# Peripherals.net
KiCad netlist of a schematic drawn in Altium Designer
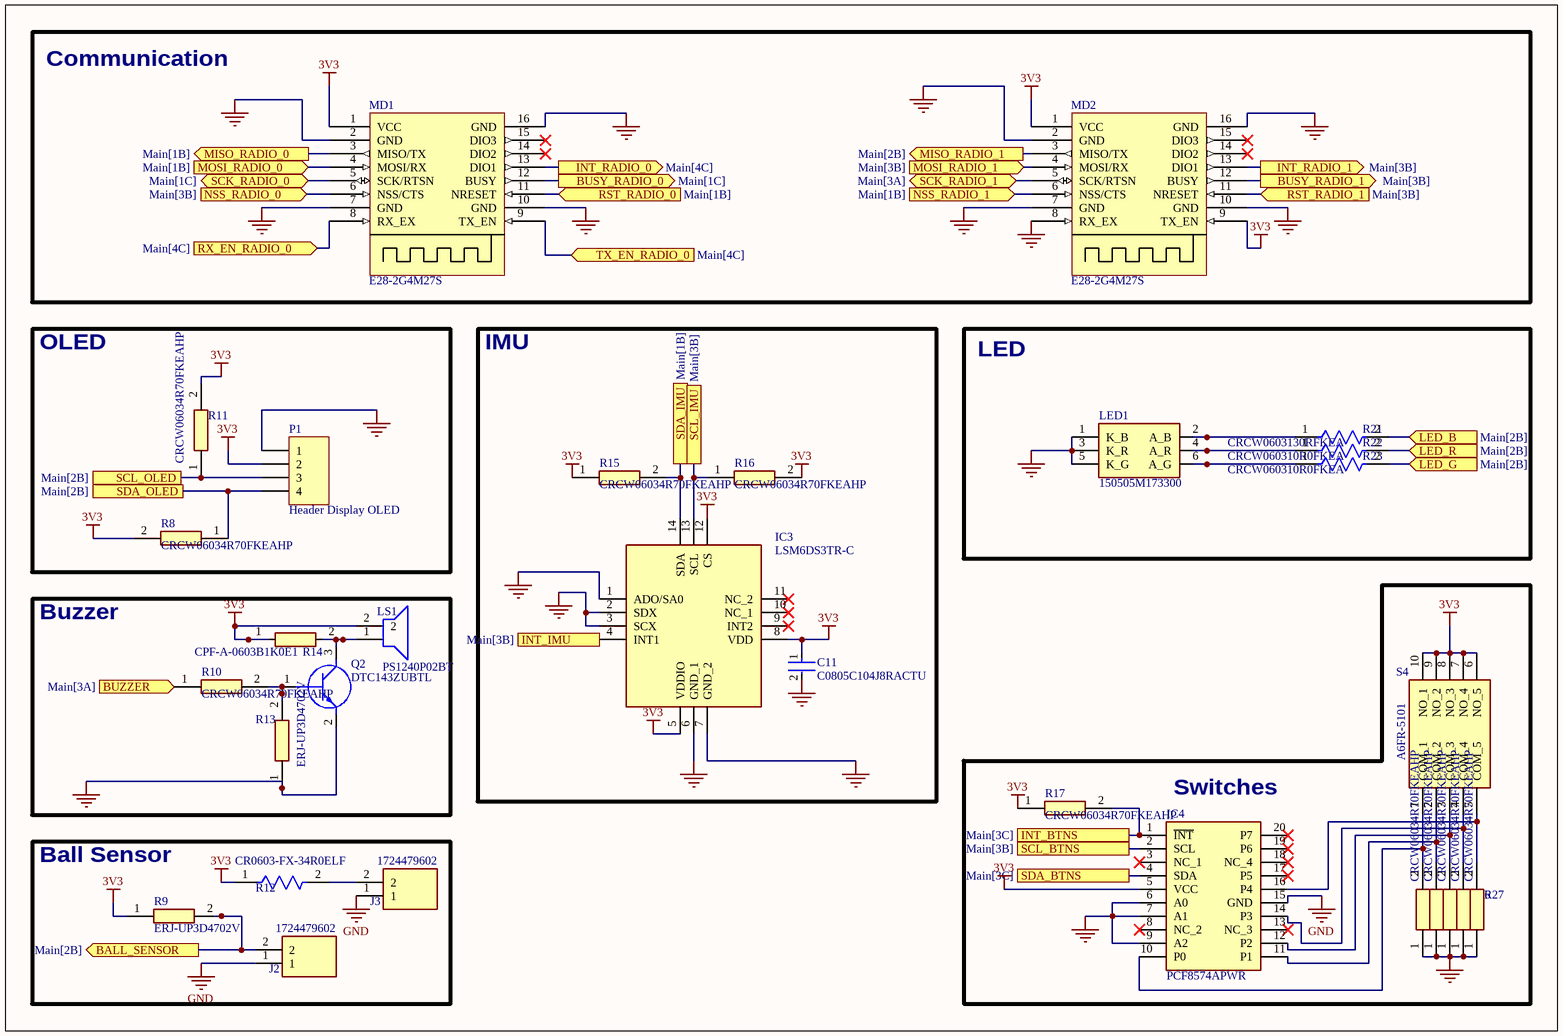
[diagram p0: Peripherals.SchDoc]

(export (version "E")
  (design (tool "Eeschema 10.0.6"))
  (components
    (comp (ref "C11")
      (value "C0805C104J8RACTU")
      (footprint "FP-C0805C-DN-MFG")
      (description "CAP CER 0.1UF 10V 5% X7R 0805")
      (fields (field (name "MANUFACTURER") "KEMET") (field (name "TOLERANCE") "0.05"))
      (libsource (lib "Altium Content Vault") (part "b4654b650e69147ec39a6b967a45e02"))
    )
    (comp (ref "IC3")
      (value "LSM6DS3TR-C")
      (footprint "roboime:LGA-14(2.5X3X0.86)")
      (description "Integrated Circuit")
      (fields (field (name "MOUSER PART NUMBER") "511-LSM6DS3TR-C"))
      (libsource (lib "roboime") (part "LSM6DS3TR-C"))
    )
    (comp (ref "IC4")
      (value "PCF8574APWR")
      (footprint "roboime:SOP65P640X120-20N")
      (description "Integrated Circuit")
      (fields (field (name "MOUSER PART NUMBER") "595-PCF8574APWR"))
      (libsource (lib "roboime") (part "PCF8574APWR"))
    )
    (comp (ref "J2")
      (value "1724479602")
      (footprint "roboime:172447_94959697_02")
      (description "Connector")
      (libsource (lib "roboime") (part "1724479602"))
    )
    (comp (ref "J3")
      (value "1724479602")
      (footprint "roboime:172447_94959697_02")
      (description "Connector")
      (libsource (lib "roboime") (part "1724479602"))
    )
    (comp (ref "LED1")
      (value "150505M173300")
      (footprint "roboime:150505M173300")
      (description "LED")
      (fields (field (name "MOUSER PART NUMBER") "710-150505M173300"))
      (libsource (lib "roboime") (part "150505M173300"))
    )
    (comp (ref "LS1")
      (value "PS1240P02BT")
      (footprint "roboime:PS1240P02BT")
      (description "Loudspeaker or Buzzer")
      (fields (field (name "MOUSER PART NUMBER") "810-PS1240P02BT"))
      (libsource (lib "roboime") (part "PS1240P02BT"))
    )
    (comp (ref "MD1")
      (value "E28-2G4M27S")
      (footprint "roboime:E28-2G4M27S")
      (description "E28-2G4M27S Ebyte SX1280 Module")
      (libsource (lib "roboime") (part "E28-2G4M27S"))
    )
    (comp (ref "MD2")
      (value "E28-2G4M27S")
      (footprint "roboime:E28-2G4M27S")
      (description "E28-2G4M27S Ebyte SX1280 Module")
      (libsource (lib "roboime") (part "E28-2G4M27S"))
    )
    (comp (ref "P1")
      (value "Header Display OLED")
      (footprint "roboime:OLED")
      (description "Header, 4-Pin")
      (fields (field (name "PUBLISHER") "Altium Limited"))
      (libsource (lib "roboime") (part "Header Display OLED"))
    )
    (comp (ref "Q2")
      (value "DTC143ZUBTL")
      (footprint "roboime:SOTFL65P210X105-3N")
      (description "Transistor BJT NPN")
      (fields (field (name "MOUSER PART NUMBER") "755-DTC143ZUBTL"))
      (libsource (lib "roboime") (part "DTC143ZUBTL"))
    )
    (comp (ref "R8")
      (value "CRCW06034R70FKEAHP")
      (footprint "roboime:RESC1608X55N")
      (description "Resistor")
      (fields (field (name "MOUSER PART NUMBER") "71-CRCW06034R70FKEAH"))
      (libsource (lib "") (part "CRCW06034R70FKEAHP_2"))
    )
    (comp (ref "R9")
      (value "ERJ-UP3D4702V")
      (footprint "roboime:ERJUP3")
      (description "Resistor")
      (fields (field (name "MOUSER PART NUMBER") "667-ERJ-UP3D4702V"))
      (libsource (lib "roboime") (part "ERJ-UP3D4702V"))
    )
    (comp (ref "R10")
      (value "CRCW06034R70FKEAHP")
      (footprint "roboime:RESC1608X55N")
      (description "Resistor")
      (fields (field (name "MOUSER PART NUMBER") "71-CRCW06034R70FKEAH"))
      (libsource (lib "") (part "CRCW06034R70FKEAHP_1"))
    )
    (comp (ref "R11")
      (value "CRCW06034R70FKEAHP")
      (footprint "roboime:RESC1608X55N")
      (description "Resistor")
      (fields (field (name "MOUSER PART NUMBER") "71-CRCW06034R70FKEAH"))
      (libsource (lib "roboime") (part "CRCW06034R70FKEAHP"))
    )
    (comp (ref "R12")
      (value "CR0603-FX-34R0ELF")
      (footprint "FP-CR0603-MFG")
      (description "Thick Film Chip Resistors 0603 34Ω 0.1W 1% 100ppm/°C")
      (fields (field (name "TOLERANCE") "1%"))
      (libsource (lib "Altium Content Vault") (part "1029c3af85768c4190bb7ad29bc67b5"))
    )
    (comp (ref "R13")
      (value "ERJ-UP3D4702V")
      (footprint "roboime:ERJUP3")
      (description "Resistor")
      (fields (field (name "MOUSER PART NUMBER") "667-ERJ-UP3D4702V"))
      (libsource (lib "") (part "ERJ-UP3D4702V_1"))
    )
    (comp (ref "R14")
      (value "CPF-A-0603B1K0E1")
      (footprint "roboime:RESC1608X55N")
      (description "Resistor")
      (fields (field (name "MOUSER PART NUMBER") "279-CPF-A-0603B1K0E1"))
      (libsource (lib "roboime") (part "CPF-A-0603B1K0E1"))
    )
    (comp (ref "R15")
      (value "CRCW06034R70FKEAHP")
      (footprint "roboime:RESC1608X55N")
      (description "Resistor")
      (fields (field (name "MOUSER PART NUMBER") "71-CRCW06034R70FKEAH"))
      (libsource (lib "") (part "CRCW06034R70FKEAHP_1"))
    )
    (comp (ref "R16")
      (value "CRCW06034R70FKEAHP")
      (footprint "roboime:RESC1608X55N")
      (description "Resistor")
      (fields (field (name "MOUSER PART NUMBER") "71-CRCW06034R70FKEAH"))
      (libsource (lib "") (part "CRCW06034R70FKEAHP_1"))
    )
    (comp (ref "R17")
      (value "CRCW06034R70FKEAHP")
      (footprint "roboime:RESC1608X55N")
      (description "Resistor")
      (fields (field (name "MOUSER PART NUMBER") "71-CRCW06034R70FKEAH"))
      (libsource (lib "") (part "CRCW06034R70FKEAHP_1"))
    )
    (comp (ref "R20")
      (value "CRCW06034R70FKEAHP")
      (footprint "roboime:RESC1608X55N")
      (description "Resistor")
      (fields (field (name "MOUSER PART NUMBER") "71-CRCW06034R70FKEAH"))
      (libsource (lib "roboime") (part "CRCW06034R70FKEAHP"))
    )
    (comp (ref "R21")
      (value "CRCW0603130RFKEA")
      (footprint "FP-CRCW0603-e3-IPC_A")
      (description "RES Thick Film, 130Ω, 1%, 0.1W, 100ppm/°C, 0603")
      (fields (field (name "TOLERANCE") "1%"))
      (libsource (lib "Altium Content Vault") (part "1029c3af85768c4190bb7ad29bc67b5"))
    )
    (comp (ref "R22")
      (value "CRCW060310R0FKEA")
      (footprint "FP-CRCW0603-e3-IPC_A")
      (description "RES Thick Film, 10Ω, 1%, 0.1W, 100ppm/°C, 0603")
      (fields (field (name "TOLERANCE") "1%"))
      (libsource (lib "Altium Content Vault") (part "1029c3af85768c4190bb7ad29bc67b5"))
    )
    (comp (ref "R23")
      (value "CRCW060310R0FKEA")
      (footprint "FP-CRCW0603-e3-IPC_A")
      (description "RES Thick Film, 10Ω, 1%, 0.1W, 100ppm/°C, 0603")
      (fields (field (name "TOLERANCE") "1%"))
      (libsource (lib "Altium Content Vault") (part "1029c3af85768c4190bb7ad29bc67b5"))
    )
    (comp (ref "R24")
      (value "CRCW06034R70FKEAHP")
      (footprint "roboime:RESC1608X55N")
      (description "Resistor")
      (fields (field (name "MOUSER PART NUMBER") "71-CRCW06034R70FKEAH"))
      (libsource (lib "roboime") (part "CRCW06034R70FKEAHP"))
    )
    (comp (ref "R25")
      (value "CRCW06034R70FKEAHP")
      (footprint "roboime:RESC1608X55N")
      (description "Resistor")
      (fields (field (name "MOUSER PART NUMBER") "71-CRCW06034R70FKEAH"))
      (libsource (lib "roboime") (part "CRCW06034R70FKEAHP"))
    )
    (comp (ref "R26")
      (value "CRCW06034R70FKEAHP")
      (footprint "roboime:RESC1608X55N")
      (description "Resistor")
      (fields (field (name "MOUSER PART NUMBER") "71-CRCW06034R70FKEAH"))
      (libsource (lib "roboime") (part "CRCW06034R70FKEAHP"))
    )
    (comp (ref "R27")
      (value "CRCW06034R70FKEAHP")
      (footprint "roboime:RESC1608X55N")
      (description "Resistor")
      (fields (field (name "MOUSER PART NUMBER") "71-CRCW06034R70FKEAH"))
      (libsource (lib "roboime") (part "CRCW06034R70FKEAHP"))
    )
    (comp (ref "S4")
      (value "A6FR-5101")
      (footprint "roboime:A6FR5101")
      (description "Switch")
      (fields (field (name "MOUSER PART NUMBER") "653-A6FR-5101"))
      (libsource (lib "roboime") (part "A6FR-5101"))
    )
  )
  (nets
    (net (code "1") (name "/BALL_SENSOR") (class "Default")
      (node (ref "J2") (pin "2") (pinfunction "2_2") (pintype "passive"))
      (node (ref "R9") (pin "2") (pinfunction "2_2") (pintype "passive"))
    )
    (net (code "2") (name "/BUSY_RADIO_0") (class "Default")
      (node (ref "MD1") (pin "12") (pinfunction "BUSY_12") (pintype "output"))
    )
    (net (code "3") (name "/BUSY_RADIO_1") (class "Default")
      (node (ref "MD2") (pin "12") (pinfunction "BUSY_12") (pintype "output"))
    )
    (net (code "4") (name "/BUZZER") (class "Default")
      (node (ref "R10") (pin "1") (pinfunction "1_1") (pintype "passive"))
    )
    (net (code "5") (name "/INT_BTNS") (class "Default")
      (node (ref "IC4") (pin "1") (pinfunction "~{INT}_1") (pintype "passive"))
      (node (ref "R17") (pin "2") (pinfunction "2_2") (pintype "passive"))
    )
    (net (code "6") (name "/INT_IMU") (class "Default")
      (node (ref "IC3") (pin "4") (pinfunction "INT1_4") (pintype "passive"))
    )
    (net (code "7") (name "/INT_RADIO_0") (class "Default")
      (node (ref "MD1") (pin "13") (pinfunction "DIO1_13") (pintype "output"))
    )
    (net (code "8") (name "/INT_RADIO_1") (class "Default")
      (node (ref "MD2") (pin "13") (pinfunction "DIO1_13") (pintype "output"))
    )
    (net (code "9") (name "/LED_B") (class "Default")
      (node (ref "R21") (pin "2") (pinfunction "2_2") (pintype "passive"))
    )
    (net (code "10") (name "/LED_G") (class "Default")
      (node (ref "R23") (pin "2") (pinfunction "2_2") (pintype "passive"))
    )
    (net (code "11") (name "/LED_R") (class "Default")
      (node (ref "R22") (pin "2") (pinfunction "2_2") (pintype "passive"))
    )
    (net (code "12") (name "/MISO_RADIO_0") (class "Default")
      (node (ref "MD1") (pin "3") (pinfunction "MISO/TX_3") (pintype "output"))
    )
    (net (code "13") (name "/MISO_RADIO_1") (class "Default")
      (node (ref "MD2") (pin "3") (pinfunction "MISO/TX_3") (pintype "output"))
    )
    (net (code "14") (name "/MOSI_RADIO_0") (class "Default")
      (node (ref "MD1") (pin "4") (pinfunction "MOSI/RX_4") (pintype "input"))
    )
    (net (code "15") (name "/MOSI_RADIO_1") (class "Default")
      (node (ref "MD2") (pin "4") (pinfunction "MOSI/RX_4") (pintype "input"))
    )
    (net (code "16") (name "/NSS_RADIO_0") (class "Default")
      (node (ref "MD1") (pin "6") (pinfunction "NSS/CTS_6") (pintype "input"))
    )
    (net (code "17") (name "/NSS_RADIO_1") (class "Default")
      (node (ref "MD2") (pin "6") (pinfunction "NSS/CTS_6") (pintype "input"))
    )
    (net (code "18") (name "/RST_RADIO_0") (class "Default")
      (node (ref "MD1") (pin "11") (pinfunction "NRESET_11") (pintype "input"))
    )
    (net (code "19") (name "/RST_RADIO_1") (class "Default")
      (node (ref "MD2") (pin "11") (pinfunction "NRESET_11") (pintype "input"))
    )
    (net (code "20") (name "/RX_EN_RADIO_0") (class "Default")
      (node (ref "MD1") (pin "8") (pinfunction "RX_EX_8") (pintype "input"))
    )
    (net (code "21") (name "/SCK_RADIO_0") (class "Default")
      (node (ref "MD1") (pin "5") (pinfunction "SCK/RTSN_5") (pintype "bidirectional"))
    )
    (net (code "22") (name "/SCK_RADIO_1") (class "Default")
      (node (ref "MD2") (pin "5") (pinfunction "SCK/RTSN_5") (pintype "bidirectional"))
    )
    (net (code "23") (name "/SCL_BTNS") (class "Default")
      (node (ref "IC4") (pin "2") (pinfunction "SCL_2") (pintype "passive"))
    )
    (net (code "24") (name "/SCL_IMU") (class "Default")
      (node (ref "IC3") (pin "13") (pinfunction "SCL_13") (pintype "passive"))
      (node (ref "R16") (pin "1") (pinfunction "1_1") (pintype "passive"))
    )
    (net (code "25") (name "/SCL_OLED") (class "Default")
      (node (ref "P1") (pin "3") (pinfunction "3_3") (pintype "passive"))
      (node (ref "R11") (pin "1") (pinfunction "1_1") (pintype "passive"))
    )
    (net (code "26") (name "/SDA_BTNS") (class "Default")
      (node (ref "IC4") (pin "4") (pinfunction "SDA_4") (pintype "passive"))
    )
    (net (code "27") (name "/SDA_IMU") (class "Default")
      (node (ref "IC3") (pin "14") (pinfunction "SDA_14") (pintype "passive"))
      (node (ref "R15") (pin "2") (pinfunction "2_2") (pintype "passive"))
    )
    (net (code "28") (name "/SDA_OLED") (class "Default")
      (node (ref "P1") (pin "4") (pinfunction "4_4") (pintype "passive"))
      (node (ref "R8") (pin "1") (pinfunction "1_1") (pintype "passive"))
    )
    (net (code "29") (name "/TX_EN_RADIO_0") (class "Default")
      (node (ref "MD1") (pin "9") (pinfunction "TX_EN_9") (pintype "input"))
    )
    (net (code "30") (name "3V3") (class "Default")
      (node (ref "C11") (pin "1") (pinfunction "1_1") (pintype "passive"))
      (node (ref "IC3") (pin "12") (pinfunction "CS_12") (pintype "passive"))
      (node (ref "IC3") (pin "5") (pinfunction "VDDIO_5") (pintype "passive"))
      (node (ref "IC3") (pin "8") (pinfunction "VDD_8") (pintype "passive"))
      (node (ref "IC4") (pin "5") (pinfunction "VCC_5") (pintype "passive"))
      (node (ref "LS1") (pin "2") (pinfunction "2_2") (pintype "passive"))
      (node (ref "MD1") (pin "1") (pinfunction "VCC_1") (pintype "power_in"))
      (node (ref "MD2") (pin "1") (pinfunction "VCC_1") (pintype "power_in"))
      (node (ref "MD2") (pin "9") (pinfunction "TX_EN_9") (pintype "input"))
      (node (ref "P1") (pin "2") (pinfunction "2_2") (pintype "passive"))
      (node (ref "R11") (pin "2") (pinfunction "2_2") (pintype "passive"))
      (node (ref "R12") (pin "1") (pinfunction "1_1") (pintype "passive"))
      (node (ref "R14") (pin "1") (pinfunction "1_1") (pintype "passive"))
      (node (ref "R15") (pin "1") (pinfunction "1_1") (pintype "passive"))
      (node (ref "R16") (pin "2") (pinfunction "2_2") (pintype "passive"))
      (node (ref "R17") (pin "1") (pinfunction "1_1") (pintype "passive"))
      (node (ref "R8") (pin "2") (pinfunction "2_2") (pintype "passive"))
      (node (ref "R9") (pin "1") (pinfunction "1_1") (pintype "passive"))
      (node (ref "S4") (pin "10") (pinfunction "NO_1_10") (pintype "passive"))
      (node (ref "S4") (pin "6") (pinfunction "NO_5_6") (pintype "passive"))
      (node (ref "S4") (pin "7") (pinfunction "NO_4_7") (pintype "passive"))
      (node (ref "S4") (pin "8") (pinfunction "NO_3_8") (pintype "passive"))
      (node (ref "S4") (pin "9") (pinfunction "NO_2_9") (pintype "passive"))
    )
    (net (code "31") (name "GND") (class "Default")
      (node (ref "C11") (pin "2") (pinfunction "2_2") (pintype "passive"))
      (node (ref "IC3") (pin "1") (pinfunction "ADO/SA0_1") (pintype "passive"))
      (node (ref "IC3") (pin "2") (pinfunction "SDX_2") (pintype "passive"))
      (node (ref "IC3") (pin "3") (pinfunction "SCX_3") (pintype "passive"))
      (node (ref "IC3") (pin "6") (pinfunction "GND_1_6") (pintype "passive"))
      (node (ref "IC3") (pin "7") (pinfunction "GND_2_7") (pintype "passive"))
      (node (ref "IC4") (pin "15") (pinfunction "GND_15") (pintype "passive"))
      (node (ref "IC4") (pin "6") (pinfunction "A0_6") (pintype "passive"))
      (node (ref "IC4") (pin "7") (pinfunction "A1_7") (pintype "passive"))
      (node (ref "IC4") (pin "9") (pinfunction "A2_9") (pintype "passive"))
      (node (ref "J2") (pin "1") (pinfunction "1_1") (pintype "passive"))
      (node (ref "J3") (pin "1") (pinfunction "1_1") (pintype "passive"))
      (node (ref "LED1") (pin "1") (pinfunction "K_B_1") (pintype "passive"))
      (node (ref "LED1") (pin "3") (pinfunction "K_R_3") (pintype "passive"))
      (node (ref "LED1") (pin "5") (pinfunction "K_G_5") (pintype "passive"))
      (node (ref "MD1") (pin "10") (pinfunction "GND_10") (pintype "power_in"))
      (node (ref "MD1") (pin "16") (pinfunction "GND_16") (pintype "power_in"))
      (node (ref "MD1") (pin "2") (pinfunction "GND_2") (pintype "power_in"))
      (node (ref "MD1") (pin "7") (pinfunction "GND_7") (pintype "power_in"))
      (node (ref "MD2") (pin "10") (pinfunction "GND_10") (pintype "power_in"))
      (node (ref "MD2") (pin "16") (pinfunction "GND_16") (pintype "power_in"))
      (node (ref "MD2") (pin "2") (pinfunction "GND_2") (pintype "power_in"))
      (node (ref "MD2") (pin "7") (pinfunction "GND_7") (pintype "power_in"))
      (node (ref "MD2") (pin "8") (pinfunction "RX_EX_8") (pintype "input"))
      (node (ref "P1") (pin "1") (pinfunction "1_1") (pintype "passive"))
      (node (ref "Q2") (pin "2") (pinfunction "E_2") (pintype "passive"))
      (node (ref "R13") (pin "1") (pinfunction "1_1") (pintype "passive"))
      (node (ref "R20") (pin "1") (pinfunction "1_1") (pintype "passive"))
      (node (ref "R24") (pin "1") (pinfunction "1_1") (pintype "passive"))
      (node (ref "R25") (pin "1") (pinfunction "1_1") (pintype "passive"))
      (node (ref "R26") (pin "1") (pinfunction "1_1") (pintype "passive"))
      (node (ref "R27") (pin "1") (pinfunction "1_1") (pintype "passive"))
    )
    (net (code "32") (name "Net-(IC4-P0)") (class "Default")
      (node (ref "IC4") (pin "10") (pinfunction "P0_10") (pintype "passive"))
      (node (ref "R20") (pin "2") (pinfunction "2_2") (pintype "passive"))
      (node (ref "S4") (pin "1") (pinfunction "COM_1_1") (pintype "passive"))
    )
    (net (code "33") (name "Net-(IC4-P1)") (class "Default")
      (node (ref "IC4") (pin "11") (pinfunction "P1_11") (pintype "passive"))
      (node (ref "R24") (pin "2") (pinfunction "2_2") (pintype "passive"))
      (node (ref "S4") (pin "2") (pinfunction "COM_2_2") (pintype "passive"))
    )
    (net (code "34") (name "Net-(IC4-P2)") (class "Default")
      (node (ref "IC4") (pin "12") (pinfunction "P2_12") (pintype "passive"))
      (node (ref "R25") (pin "2") (pinfunction "2_2") (pintype "passive"))
      (node (ref "S4") (pin "3") (pinfunction "COM_3_3") (pintype "passive"))
    )
    (net (code "35") (name "Net-(IC4-P3)") (class "Default")
      (node (ref "IC4") (pin "14") (pinfunction "P3_14") (pintype "passive"))
      (node (ref "R26") (pin "2") (pinfunction "2_2") (pintype "passive"))
      (node (ref "S4") (pin "4") (pinfunction "COM_4_4") (pintype "passive"))
    )
    (net (code "36") (name "Net-(IC4-P4)") (class "Default")
      (node (ref "IC4") (pin "16") (pinfunction "P4_16") (pintype "passive"))
      (node (ref "R27") (pin "2") (pinfunction "2_2") (pintype "passive"))
      (node (ref "S4") (pin "5") (pinfunction "COM_5_5") (pintype "passive"))
    )
    (net (code "37") (name "Net-(J3-Pad2)") (class "Default")
      (node (ref "J3") (pin "2") (pinfunction "2_2") (pintype "passive"))
      (node (ref "R12") (pin "2") (pinfunction "2_2") (pintype "passive"))
    )
    (net (code "38") (name "Net-(LED1-A_B)") (class "Default")
      (node (ref "LED1") (pin "2") (pinfunction "A_B_2") (pintype "passive"))
      (node (ref "R21") (pin "1") (pinfunction "1_1") (pintype "passive"))
    )
    (net (code "39") (name "Net-(LED1-A_G)") (class "Default")
      (node (ref "LED1") (pin "6") (pinfunction "A_G_6") (pintype "passive"))
      (node (ref "R23") (pin "1") (pinfunction "1_1") (pintype "passive"))
    )
    (net (code "40") (name "Net-(LED1-A_R)") (class "Default")
      (node (ref "LED1") (pin "4") (pinfunction "A_R_4") (pintype "passive"))
      (node (ref "R22") (pin "1") (pinfunction "1_1") (pintype "passive"))
    )
    (net (code "41") (name "Net-(Q2-B)") (class "Default")
      (node (ref "Q2") (pin "1") (pinfunction "B_1") (pintype "passive"))
      (node (ref "R10") (pin "2") (pinfunction "2_2") (pintype "passive"))
      (node (ref "R13") (pin "2") (pinfunction "2_2") (pintype "passive"))
    )
    (net (code "42") (name "Net-(Q2-C)") (class "Default")
      (node (ref "LS1") (pin "1") (pintype "passive"))
      (node (ref "Q2") (pin "3") (pinfunction "C_3") (pintype "passive"))
      (node (ref "R14") (pin "2") (pinfunction "2_2") (pintype "passive"))
    )
    (net (code "43") (name "unconnected-(IC3-INT2-Pad9)") (class "Default")
      (node (ref "IC3") (pin "9") (pinfunction "INT2_9") (pintype "passive+no_connect"))
    )
    (net (code "44") (name "unconnected-(IC3-NC_1-Pad10)") (class "Default")
      (node (ref "IC3") (pin "10") (pinfunction "NC_1_10") (pintype "passive+no_connect"))
    )
    (net (code "45") (name "unconnected-(IC3-NC_2-Pad11)") (class "Default")
      (node (ref "IC3") (pin "11") (pinfunction "NC_2_11") (pintype "passive+no_connect"))
    )
    (net (code "46") (name "unconnected-(IC4-NC_1-Pad3)") (class "Default")
      (node (ref "IC4") (pin "3") (pinfunction "NC_1_3") (pintype "passive+no_connect"))
    )
    (net (code "47") (name "unconnected-(IC4-NC_2-Pad8)") (class "Default")
      (node (ref "IC4") (pin "8") (pinfunction "NC_2_8") (pintype "passive+no_connect"))
    )
    (net (code "48") (name "unconnected-(IC4-NC_3-Pad13)") (class "Default")
      (node (ref "IC4") (pin "13") (pinfunction "NC_3_13") (pintype "passive+no_connect"))
    )
    (net (code "49") (name "unconnected-(IC4-NC_4-Pad18)") (class "Default")
      (node (ref "IC4") (pin "18") (pinfunction "NC_4_18") (pintype "passive+no_connect"))
    )
    (net (code "50") (name "unconnected-(IC4-P5-Pad17)") (class "Default")
      (node (ref "IC4") (pin "17") (pinfunction "P5_17") (pintype "passive+no_connect"))
    )
    (net (code "51") (name "unconnected-(IC4-P6-Pad19)") (class "Default")
      (node (ref "IC4") (pin "19") (pinfunction "P6_19") (pintype "passive+no_connect"))
    )
    (net (code "52") (name "unconnected-(IC4-P7-Pad20)") (class "Default")
      (node (ref "IC4") (pin "20") (pinfunction "P7_20") (pintype "passive+no_connect"))
    )
    (net (code "53") (name "unconnected-(MD1-DIO2-Pad14)") (class "Default")
      (node (ref "MD1") (pin "14") (pinfunction "DIO2_14") (pintype "output+no_connect"))
    )
    (net (code "54") (name "unconnected-(MD1-DIO3-Pad15)") (class "Default")
      (node (ref "MD1") (pin "15") (pinfunction "DIO3_15") (pintype "output+no_connect"))
    )
    (net (code "55") (name "unconnected-(MD2-DIO2-Pad14)") (class "Default")
      (node (ref "MD2") (pin "14") (pinfunction "DIO2_14") (pintype "output+no_connect"))
    )
    (net (code "56") (name "unconnected-(MD2-DIO3-Pad15)") (class "Default")
      (node (ref "MD2") (pin "15") (pinfunction "DIO3_15") (pintype "output+no_connect"))
    )
  )
)
